# IM69D130_MEMS_Microphone.net
KiCad netlist of a schematic drawn in Altium Designer
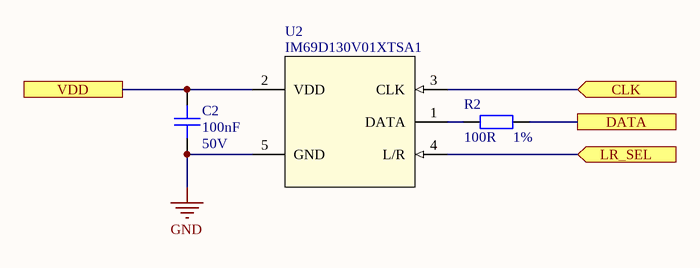
[diagram p0: IM69D130_MEMS_Microphone.SchDoc]

(export (version "E")
  (design (tool "Eeschema 10.0.6"))
  (components
    (comp (ref "C2")
      (value "CAP CER 0.1UF 50V X7R 0402")
      (footprint "C0402")
      (description "0.1µF ±10% 50V Ceramic Capacitor X7R 0402 (1005 Metric)")
      (fields
        (field (name "MANUFACTURER") "TDK")
        (field (name "MANUFACTURER PART NUMBER") "CGA2B3X7R1H104K050BB")
        (field (name "CAPACITANCE") "100nF")
        (field (name "VOLTAGE") "50V")
      )
      (libsource (lib "capacitors_smd") (part "CAP CER 0.1UF 50V X7R 0402"))
    )
    (comp (ref "R2")
      (value "RES SMD 100 OHM 1% 1/16W 0402")
      (footprint "0402R")
      (description "100 Ohms ±1% 0.063W, 1/16W Chip Resistor 0402 (1005 Metric) Moisture Resistant Thick Film")
      (fields
        (field (name "MANUFACTURER") "Yageo")
        (field (name "MANUFACTURER PART NUMBER") "RC0402FR-07100RL")
        (field (name "TOLERANCE") "1%")
        (field (name "RESISTANCE") "100R")
      )
      (libsource (lib "resistors_smd") (part "RES SMD 100 OHM 1% 1/16W 0402"))
    )
    (comp (ref "U2")
      (value "IM69D130V01XTSA1")
      (footprint "MIC_IM69D130V01XTSA1")
      (fields (field (name "MANUFACTURER") "Infineon"))
      (libsource (lib "BLDC_Motor_Driver") (part "IC IM69D130 MICROPHONE MEMS DIGITAL PDM OMNI"))
    )
  )
  (nets
    (net (code "1") (name "/CLK") (class "Default")
      (node (ref "U2") (pin "3") (pinfunction "CLK_3") (pintype "input"))
    )
    (net (code "2") (name "/DATA") (class "Default")
      (node (ref "R2") (pin "1") (pinfunction "1_1") (pintype "passive"))
    )
    (net (code "3") (name "/LR_SEL") (class "Default")
      (node (ref "U2") (pin "4") (pinfunction "L/R_4") (pintype "input"))
    )
    (net (code "4") (name "/VDD") (class "Default")
      (node (ref "C2") (pin "2") (pinfunction "2_2") (pintype "passive"))
      (node (ref "U2") (pin "2") (pinfunction "VDD_2") (pintype "power_in"))
    )
    (net (code "5") (name "GND") (class "Default")
      (node (ref "C2") (pin "1") (pinfunction "1_1") (pintype "passive"))
      (node (ref "U2") (pin "5") (pinfunction "GND_5") (pintype "power_in"))
    )
    (net (code "6") (name "Net-(U2-DATA)") (class "Default")
      (node (ref "R2") (pin "2") (pinfunction "2_2") (pintype "passive"))
      (node (ref "U2") (pin "1") (pinfunction "DATA_1") (pintype "tri_state"))
    )
  )
)
